# jubeat_io_board.net
KiCad netlist of a schematic drawn in Altium Designer
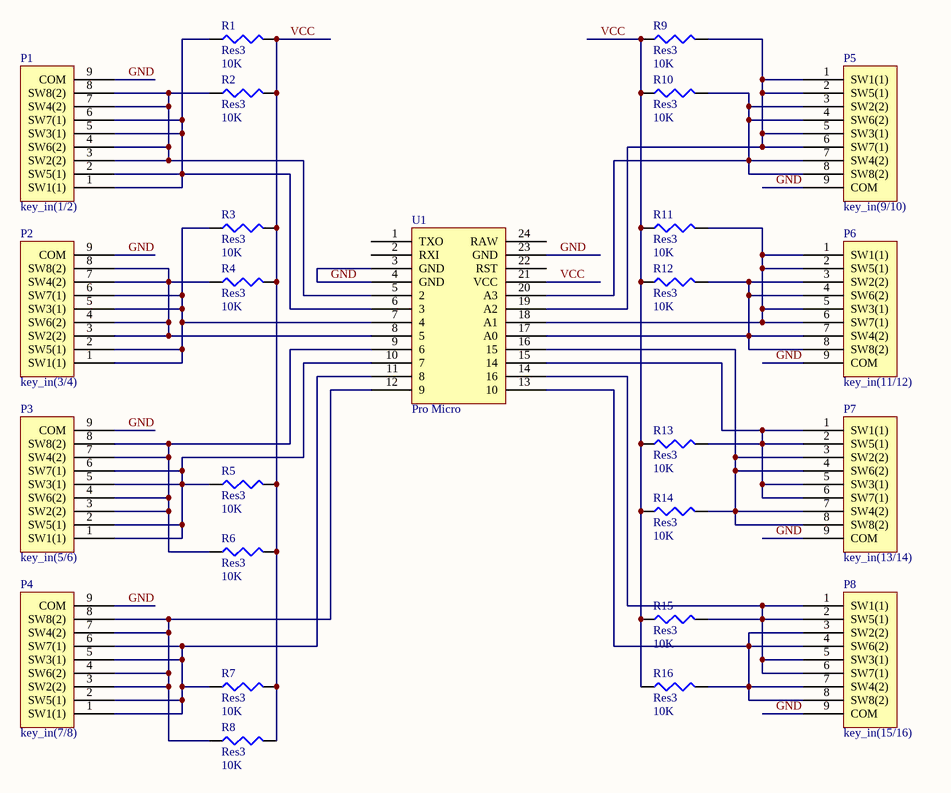
[diagram p0: jubeat_io_board.SchDoc]

(export (version "E")
  (design (tool "Eeschema 10.0.6"))
  (components
    (comp (ref "P1")
      (value "key_in(1/2)")
      (footprint "PH2.0-WI-9P")
      (description "Button PCB Board Connector, PH2.00mm")
      (libsource (lib "") (part "key_in_1"))
    )
    (comp (ref "P2")
      (value "key_in(3/4)")
      (footprint "PH2.0-WI-9P")
      (description "Button PCB Board Connector, PH2.00mm")
      (libsource (lib "") (part "key_in_1"))
    )
    (comp (ref "P3")
      (value "key_in(5/6)")
      (footprint "PH2.0-WI-9P")
      (description "Button PCB Board Connector, PH2.00mm")
      (libsource (lib "") (part "key_in_1"))
    )
    (comp (ref "P4")
      (value "key_in(7/8)")
      (footprint "PH2.0-WI-9P")
      (description "Button PCB Board Connector, PH2.00mm")
      (libsource (lib "") (part "key_in_1"))
    )
    (comp (ref "P5")
      (value "key_in(9/10)")
      (footprint "PH2.0-WI-9P")
      (description "Button PCB Board Connector, PH2.00mm")
      (libsource (lib "jubeat_io") (part "key_in"))
    )
    (comp (ref "P6")
      (value "key_in(11/12)")
      (footprint "PH2.0-WI-9P")
      (description "Button PCB Board Connector, PH2.00mm")
      (libsource (lib "jubeat_io") (part "key_in"))
    )
    (comp (ref "P7")
      (value "key_in(13/14)")
      (footprint "PH2.0-WI-9P")
      (description "Button PCB Board Connector, PH2.00mm")
      (libsource (lib "jubeat_io") (part "key_in"))
    )
    (comp (ref "P8")
      (value "key_in(15/16)")
      (footprint "PH2.0-WI-9P")
      (description "Button PCB Board Connector, PH2.00mm")
      (libsource (lib "jubeat_io") (part "key_in"))
    )
    (comp (ref "R1")
      (value "Res3")
      (footprint "J1-0603")
      (description "Resistor")
      (fields (field (name "ALTIUM_VALUE") "10K") (field (name "PUBLISHER") "Altium Limited"))
      (libsource (lib "Miscellaneous Devices") (part "Res3"))
    )
    (comp (ref "R2")
      (value "Res3")
      (footprint "J1-0603")
      (description "Resistor")
      (fields (field (name "ALTIUM_VALUE") "10K") (field (name "PUBLISHER") "Altium Limited"))
      (libsource (lib "Miscellaneous Devices") (part "Res3"))
    )
    (comp (ref "R3")
      (value "Res3")
      (footprint "J1-0603")
      (description "Resistor")
      (fields (field (name "ALTIUM_VALUE") "10K") (field (name "PUBLISHER") "Altium Limited"))
      (libsource (lib "Miscellaneous Devices") (part "Res3"))
    )
    (comp (ref "R4")
      (value "Res3")
      (footprint "J1-0603")
      (description "Resistor")
      (fields (field (name "ALTIUM_VALUE") "10K") (field (name "PUBLISHER") "Altium Limited"))
      (libsource (lib "Miscellaneous Devices") (part "Res3"))
    )
    (comp (ref "R5")
      (value "Res3")
      (footprint "J1-0603")
      (description "Resistor")
      (fields (field (name "ALTIUM_VALUE") "10K") (field (name "PUBLISHER") "Altium Limited"))
      (libsource (lib "Miscellaneous Devices") (part "Res3"))
    )
    (comp (ref "R6")
      (value "Res3")
      (footprint "J1-0603")
      (description "Resistor")
      (fields (field (name "ALTIUM_VALUE") "10K") (field (name "PUBLISHER") "Altium Limited"))
      (libsource (lib "Miscellaneous Devices") (part "Res3"))
    )
    (comp (ref "R7")
      (value "Res3")
      (footprint "J1-0603")
      (description "Resistor")
      (fields (field (name "ALTIUM_VALUE") "10K") (field (name "PUBLISHER") "Altium Limited"))
      (libsource (lib "Miscellaneous Devices") (part "Res3"))
    )
    (comp (ref "R8")
      (value "Res3")
      (footprint "J1-0603")
      (description "Resistor")
      (fields (field (name "ALTIUM_VALUE") "10K") (field (name "PUBLISHER") "Altium Limited"))
      (libsource (lib "Miscellaneous Devices") (part "Res3"))
    )
    (comp (ref "R9")
      (value "Res3")
      (footprint "J1-0603")
      (description "Resistor")
      (fields (field (name "ALTIUM_VALUE") "10K") (field (name "PUBLISHER") "Altium Limited"))
      (libsource (lib "Miscellaneous Devices") (part "Res3"))
    )
    (comp (ref "R10")
      (value "Res3")
      (footprint "J1-0603")
      (description "Resistor")
      (fields (field (name "ALTIUM_VALUE") "10K") (field (name "PUBLISHER") "Altium Limited"))
      (libsource (lib "Miscellaneous Devices") (part "Res3"))
    )
    (comp (ref "R11")
      (value "Res3")
      (footprint "J1-0603")
      (description "Resistor")
      (fields (field (name "ALTIUM_VALUE") "10K") (field (name "PUBLISHER") "Altium Limited"))
      (libsource (lib "Miscellaneous Devices") (part "Res3"))
    )
    (comp (ref "R12")
      (value "Res3")
      (footprint "J1-0603")
      (description "Resistor")
      (fields (field (name "ALTIUM_VALUE") "10K") (field (name "PUBLISHER") "Altium Limited"))
      (libsource (lib "Miscellaneous Devices") (part "Res3"))
    )
    (comp (ref "R13")
      (value "Res3")
      (footprint "J1-0603")
      (description "Resistor")
      (fields (field (name "ALTIUM_VALUE") "10K") (field (name "PUBLISHER") "Altium Limited"))
      (libsource (lib "Miscellaneous Devices") (part "Res3"))
    )
    (comp (ref "R14")
      (value "Res3")
      (footprint "J1-0603")
      (description "Resistor")
      (fields (field (name "ALTIUM_VALUE") "10K") (field (name "PUBLISHER") "Altium Limited"))
      (libsource (lib "Miscellaneous Devices") (part "Res3"))
    )
    (comp (ref "R15")
      (value "Res3")
      (footprint "J1-0603")
      (description "Resistor")
      (fields (field (name "ALTIUM_VALUE") "10K") (field (name "PUBLISHER") "Altium Limited"))
      (libsource (lib "Miscellaneous Devices") (part "Res3"))
    )
    (comp (ref "R16")
      (value "Res3")
      (footprint "J1-0603")
      (description "Resistor")
      (fields (field (name "ALTIUM_VALUE") "10K") (field (name "PUBLISHER") "Altium Limited"))
      (libsource (lib "Miscellaneous Devices") (part "Res3"))
    )
    (comp (ref "U1")
      (value "Pro Micro")
      (footprint "PRO MICRO")
      (description "Pro Micro Arduino Board")
      (libsource (lib "jubeat_io") (part "Pro Micro"))
    )
  )
  (nets
    (net (code "1") (name "/GND") (class "Default")
      (node (ref "P1") (pin "9") (pinfunction "COM_9") (pintype "passive"))
      (node (ref "P2") (pin "9") (pinfunction "COM_9") (pintype "passive"))
      (node (ref "P3") (pin "9") (pinfunction "COM_9") (pintype "passive"))
      (node (ref "P4") (pin "9") (pinfunction "COM_9") (pintype "passive"))
      (node (ref "P5") (pin "9") (pinfunction "COM_9") (pintype "passive"))
      (node (ref "P6") (pin "9") (pinfunction "COM_9") (pintype "passive"))
      (node (ref "P7") (pin "9") (pinfunction "COM_9") (pintype "passive"))
      (node (ref "P8") (pin "9") (pinfunction "COM_9") (pintype "passive"))
      (node (ref "U1") (pin "23") (pinfunction "GND_23") (pintype "passive"))
      (node (ref "U1") (pin "3") (pinfunction "GND_3") (pintype "passive"))
      (node (ref "U1") (pin "4") (pinfunction "GND_4") (pintype "passive"))
    )
    (net (code "2") (name "/VCC") (class "Default")
      (node (ref "R1") (pin "2") (pinfunction "2_2") (pintype "passive"))
      (node (ref "R10") (pin "1") (pinfunction "1_1") (pintype "passive"))
      (node (ref "R11") (pin "1") (pinfunction "1_1") (pintype "passive"))
      (node (ref "R12") (pin "1") (pinfunction "1_1") (pintype "passive"))
      (node (ref "R13") (pin "1") (pinfunction "1_1") (pintype "passive"))
      (node (ref "R14") (pin "1") (pinfunction "1_1") (pintype "passive"))
      (node (ref "R15") (pin "1") (pinfunction "1_1") (pintype "passive"))
      (node (ref "R16") (pin "1") (pinfunction "1_1") (pintype "passive"))
      (node (ref "R2") (pin "2") (pinfunction "2_2") (pintype "passive"))
      (node (ref "R3") (pin "2") (pinfunction "2_2") (pintype "passive"))
      (node (ref "R4") (pin "2") (pinfunction "2_2") (pintype "passive"))
      (node (ref "R5") (pin "2") (pinfunction "2_2") (pintype "passive"))
      (node (ref "R6") (pin "2") (pinfunction "2_2") (pintype "passive"))
      (node (ref "R7") (pin "2") (pinfunction "2_2") (pintype "passive"))
      (node (ref "R8") (pin "2") (pinfunction "2_2") (pintype "passive"))
      (node (ref "R9") (pin "1") (pinfunction "1_1") (pintype "passive"))
      (node (ref "U1") (pin "21") (pinfunction "VCC_21") (pintype "passive"))
    )
    (net (code "3") (name "Net-(P1-SW1(1))") (class "Default")
      (node (ref "P1") (pin "1") (pinfunction "SW1(1)_1") (pintype "passive"))
      (node (ref "P1") (pin "2") (pinfunction "SW5(1)_2") (pintype "passive"))
      (node (ref "P1") (pin "5") (pinfunction "SW3(1)_5") (pintype "passive"))
      (node (ref "P1") (pin "6") (pinfunction "SW7(1)_6") (pintype "passive"))
      (node (ref "R1") (pin "1") (pinfunction "1_1") (pintype "passive"))
      (node (ref "U1") (pin "6") (pinfunction "3_6") (pintype "passive"))
    )
    (net (code "4") (name "Net-(P1-SW2(2))") (class "Default")
      (node (ref "P1") (pin "3") (pinfunction "SW2(2)_3") (pintype "passive"))
      (node (ref "P1") (pin "4") (pinfunction "SW6(2)_4") (pintype "passive"))
      (node (ref "P1") (pin "7") (pinfunction "SW4(2)_7") (pintype "passive"))
      (node (ref "P1") (pin "8") (pinfunction "SW8(2)_8") (pintype "passive"))
      (node (ref "R2") (pin "1") (pinfunction "1_1") (pintype "passive"))
      (node (ref "U1") (pin "5") (pinfunction "2_5") (pintype "passive"))
    )
    (net (code "5") (name "Net-(P2-SW1(1))") (class "Default")
      (node (ref "P2") (pin "1") (pinfunction "SW1(1)_1") (pintype "passive"))
      (node (ref "P2") (pin "2") (pinfunction "SW5(1)_2") (pintype "passive"))
      (node (ref "P2") (pin "5") (pinfunction "SW3(1)_5") (pintype "passive"))
      (node (ref "P2") (pin "6") (pinfunction "SW7(1)_6") (pintype "passive"))
      (node (ref "R3") (pin "1") (pinfunction "1_1") (pintype "passive"))
      (node (ref "U1") (pin "7") (pinfunction "4_7") (pintype "passive"))
    )
    (net (code "6") (name "Net-(P2-SW2(2))") (class "Default")
      (node (ref "P2") (pin "3") (pinfunction "SW2(2)_3") (pintype "passive"))
      (node (ref "P2") (pin "4") (pinfunction "SW6(2)_4") (pintype "passive"))
      (node (ref "P2") (pin "7") (pinfunction "SW4(2)_7") (pintype "passive"))
      (node (ref "P2") (pin "8") (pinfunction "SW8(2)_8") (pintype "passive"))
      (node (ref "R4") (pin "1") (pinfunction "1_1") (pintype "passive"))
      (node (ref "U1") (pin "8") (pinfunction "5_8") (pintype "passive"))
    )
    (net (code "7") (name "Net-(P3-SW1(1))") (class "Default")
      (node (ref "P3") (pin "1") (pinfunction "SW1(1)_1") (pintype "passive"))
      (node (ref "P3") (pin "2") (pinfunction "SW5(1)_2") (pintype "passive"))
      (node (ref "P3") (pin "5") (pinfunction "SW3(1)_5") (pintype "passive"))
      (node (ref "P3") (pin "6") (pinfunction "SW7(1)_6") (pintype "passive"))
      (node (ref "R5") (pin "1") (pinfunction "1_1") (pintype "passive"))
      (node (ref "U1") (pin "10") (pinfunction "7_10") (pintype "passive"))
    )
    (net (code "8") (name "Net-(P3-SW2(2))") (class "Default")
      (node (ref "P3") (pin "3") (pinfunction "SW2(2)_3") (pintype "passive"))
      (node (ref "P3") (pin "4") (pinfunction "SW6(2)_4") (pintype "passive"))
      (node (ref "P3") (pin "7") (pinfunction "SW4(2)_7") (pintype "passive"))
      (node (ref "P3") (pin "8") (pinfunction "SW8(2)_8") (pintype "passive"))
      (node (ref "R6") (pin "1") (pinfunction "1_1") (pintype "passive"))
      (node (ref "U1") (pin "9") (pinfunction "6_9") (pintype "passive"))
    )
    (net (code "9") (name "Net-(P4-SW1(1))") (class "Default")
      (node (ref "P4") (pin "1") (pinfunction "SW1(1)_1") (pintype "passive"))
      (node (ref "P4") (pin "2") (pinfunction "SW5(1)_2") (pintype "passive"))
      (node (ref "P4") (pin "5") (pinfunction "SW3(1)_5") (pintype "passive"))
      (node (ref "P4") (pin "6") (pinfunction "SW7(1)_6") (pintype "passive"))
      (node (ref "R7") (pin "1") (pinfunction "1_1") (pintype "passive"))
      (node (ref "U1") (pin "11") (pinfunction "8_11") (pintype "passive"))
    )
    (net (code "10") (name "Net-(P4-SW2(2))") (class "Default")
      (node (ref "P4") (pin "3") (pinfunction "SW2(2)_3") (pintype "passive"))
      (node (ref "P4") (pin "4") (pinfunction "SW6(2)_4") (pintype "passive"))
      (node (ref "P4") (pin "7") (pinfunction "SW4(2)_7") (pintype "passive"))
      (node (ref "P4") (pin "8") (pinfunction "SW8(2)_8") (pintype "passive"))
      (node (ref "R8") (pin "1") (pinfunction "1_1") (pintype "passive"))
      (node (ref "U1") (pin "12") (pinfunction "9_12") (pintype "passive"))
    )
    (net (code "11") (name "Net-(P5-SW1(1))") (class "Default")
      (node (ref "P5") (pin "1") (pinfunction "SW1(1)_1") (pintype "passive"))
      (node (ref "P5") (pin "2") (pinfunction "SW5(1)_2") (pintype "passive"))
      (node (ref "P5") (pin "5") (pinfunction "SW3(1)_5") (pintype "passive"))
      (node (ref "P5") (pin "6") (pinfunction "SW7(1)_6") (pintype "passive"))
      (node (ref "R9") (pin "2") (pinfunction "2_2") (pintype "passive"))
      (node (ref "U1") (pin "19") (pinfunction "A2_19") (pintype "passive"))
    )
    (net (code "12") (name "Net-(P5-SW2(2))") (class "Default")
      (node (ref "P5") (pin "3") (pinfunction "SW2(2)_3") (pintype "passive"))
      (node (ref "P5") (pin "4") (pinfunction "SW6(2)_4") (pintype "passive"))
      (node (ref "P5") (pin "7") (pinfunction "SW4(2)_7") (pintype "passive"))
      (node (ref "P5") (pin "8") (pinfunction "SW8(2)_8") (pintype "passive"))
      (node (ref "R10") (pin "2") (pinfunction "2_2") (pintype "passive"))
      (node (ref "U1") (pin "20") (pinfunction "A3_20") (pintype "passive"))
    )
    (net (code "13") (name "Net-(P6-SW1(1))") (class "Default")
      (node (ref "P6") (pin "1") (pinfunction "SW1(1)_1") (pintype "passive"))
      (node (ref "P6") (pin "2") (pinfunction "SW5(1)_2") (pintype "passive"))
      (node (ref "P6") (pin "5") (pinfunction "SW3(1)_5") (pintype "passive"))
      (node (ref "P6") (pin "6") (pinfunction "SW7(1)_6") (pintype "passive"))
      (node (ref "R11") (pin "2") (pinfunction "2_2") (pintype "passive"))
      (node (ref "U1") (pin "18") (pinfunction "A1_18") (pintype "passive"))
    )
    (net (code "14") (name "Net-(P6-SW2(2))") (class "Default")
      (node (ref "P6") (pin "3") (pinfunction "SW2(2)_3") (pintype "passive"))
      (node (ref "P6") (pin "4") (pinfunction "SW6(2)_4") (pintype "passive"))
      (node (ref "P6") (pin "7") (pinfunction "SW4(2)_7") (pintype "passive"))
      (node (ref "P6") (pin "8") (pinfunction "SW8(2)_8") (pintype "passive"))
      (node (ref "R12") (pin "2") (pinfunction "2_2") (pintype "passive"))
      (node (ref "U1") (pin "17") (pinfunction "A0_17") (pintype "passive"))
    )
    (net (code "15") (name "Net-(P7-SW1(1))") (class "Default")
      (node (ref "P7") (pin "1") (pinfunction "SW1(1)_1") (pintype "passive"))
      (node (ref "P7") (pin "2") (pinfunction "SW5(1)_2") (pintype "passive"))
      (node (ref "P7") (pin "5") (pinfunction "SW3(1)_5") (pintype "passive"))
      (node (ref "P7") (pin "6") (pinfunction "SW7(1)_6") (pintype "passive"))
      (node (ref "R13") (pin "2") (pinfunction "2_2") (pintype "passive"))
      (node (ref "U1") (pin "15") (pinfunction "14_15") (pintype "passive"))
    )
    (net (code "16") (name "Net-(P7-SW2(2))") (class "Default")
      (node (ref "P7") (pin "3") (pinfunction "SW2(2)_3") (pintype "passive"))
      (node (ref "P7") (pin "4") (pinfunction "SW6(2)_4") (pintype "passive"))
      (node (ref "P7") (pin "7") (pinfunction "SW4(2)_7") (pintype "passive"))
      (node (ref "P7") (pin "8") (pinfunction "SW8(2)_8") (pintype "passive"))
      (node (ref "R14") (pin "2") (pinfunction "2_2") (pintype "passive"))
      (node (ref "U1") (pin "16") (pinfunction "15_16") (pintype "passive"))
    )
    (net (code "17") (name "Net-(P8-SW1(1))") (class "Default")
      (node (ref "P8") (pin "1") (pinfunction "SW1(1)_1") (pintype "passive"))
      (node (ref "P8") (pin "2") (pinfunction "SW5(1)_2") (pintype "passive"))
      (node (ref "P8") (pin "5") (pinfunction "SW3(1)_5") (pintype "passive"))
      (node (ref "P8") (pin "6") (pinfunction "SW7(1)_6") (pintype "passive"))
      (node (ref "R15") (pin "2") (pinfunction "2_2") (pintype "passive"))
      (node (ref "U1") (pin "14") (pinfunction "16_14") (pintype "passive"))
    )
    (net (code "18") (name "Net-(P8-SW2(2))") (class "Default")
      (node (ref "P8") (pin "3") (pinfunction "SW2(2)_3") (pintype "passive"))
      (node (ref "P8") (pin "4") (pinfunction "SW6(2)_4") (pintype "passive"))
      (node (ref "P8") (pin "7") (pinfunction "SW4(2)_7") (pintype "passive"))
      (node (ref "P8") (pin "8") (pinfunction "SW8(2)_8") (pintype "passive"))
      (node (ref "R16") (pin "2") (pinfunction "2_2") (pintype "passive"))
      (node (ref "U1") (pin "13") (pinfunction "10_13") (pintype "passive"))
    )
    (net (code "19") (name "unconnected-(U1-RAW-Pad24)") (class "Default")
      (node (ref "U1") (pin "24") (pinfunction "RAW_24") (pintype "passive"))
    )
    (net (code "20") (name "unconnected-(U1-RST-Pad22)") (class "Default")
      (node (ref "U1") (pin "22") (pinfunction "RST_22") (pintype "passive"))
    )
    (net (code "21") (name "unconnected-(U1-RXI-Pad2)") (class "Default")
      (node (ref "U1") (pin "2") (pinfunction "RXI_2") (pintype "passive"))
    )
    (net (code "22") (name "unconnected-(U1-TXO-Pad1)") (class "Default")
      (node (ref "U1") (pin "1") (pinfunction "TXO_1") (pintype "passive"))
    )
  )
)
